# PowerSupply.net
KiCad netlist of a schematic drawn in Altium Designer
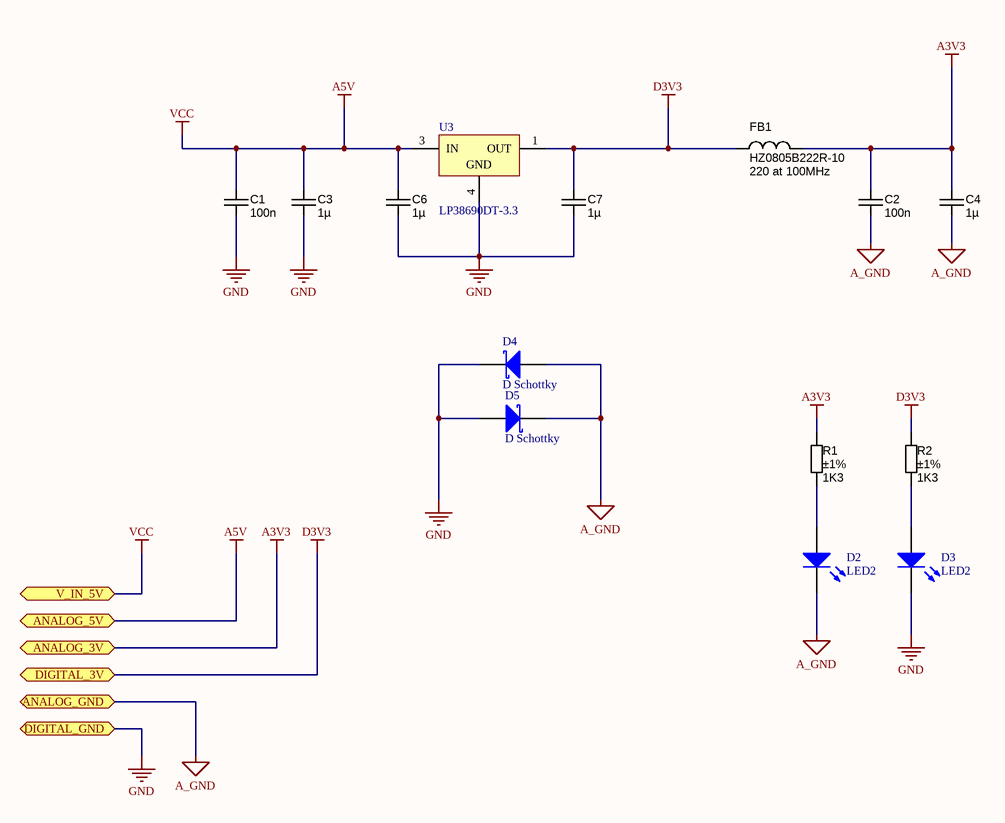
[diagram p0: PowerSupply.SchDoc]

(export (version "E")
  (design (tool "Eeschema 10.0.6"))
  (components
    (comp (ref "C1")
      (value "100n")
      (footprint "CAPC2012X135N")
      (description "Capacitor SMD Cer 100nF 10% 50V X7R 0805")
      (fields (field (name "TOLERANCE") "±10%") (field (name "Comment") "approved sub OK"))
      (libsource (lib "PBL - Capacitors") (part "CAPC_100n_0805_X7R_50V_10%"))
    )
    (comp (ref "C2")
      (value "100n")
      (footprint "CAPC2012X135N")
      (description "Capacitor SMD Cer 100nF 10% 50V X7R 0805")
      (fields (field (name "TOLERANCE") "±10%") (field (name "Comment") "approved sub OK"))
      (libsource (lib "PBL - Capacitors") (part "CAPC_100n_0805_X7R_50V_10%"))
    )
    (comp (ref "C3")
      (value "1µ")
      (footprint "CAPC2012X135N")
      (description "Capacitor SMD Cer 1uF 10% 16V X7R 0805")
      (fields (field (name "TOLERANCE") "±10%") (field (name "Comment") "approved sub OK"))
      (libsource (lib "PBL - Capacitors") (part "CAPC_1u_0805_X7R_16V_10%"))
    )
    (comp (ref "C4")
      (value "1µ")
      (footprint "CAPC2012X135N")
      (description "Capacitor SMD Cer 1uF 10% 16V X7R 0805")
      (fields (field (name "TOLERANCE") "±10%") (field (name "Comment") "approved sub OK"))
      (libsource (lib "PBL - Capacitors") (part "CAPC_1u_0805_X7R_16V_10%"))
    )
    (comp (ref "C6")
      (value "1µ")
      (footprint "CAPC2012X135N")
      (description "Capacitor SMD Cer 1uF 10% 16V X7R 0805")
      (fields (field (name "TOLERANCE") "±10%") (field (name "Comment") "approved sub OK"))
      (libsource (lib "PBL - Capacitors") (part "CAPC_1u_0805_X7R_16V_10%"))
    )
    (comp (ref "C7")
      (value "1µ")
      (footprint "CAPC2012X135N")
      (description "Capacitor SMD Cer 1uF 10% 16V X7R 0805")
      (fields (field (name "TOLERANCE") "±10%") (field (name "Comment") "approved sub OK"))
      (libsource (lib "PBL - Capacitors") (part "CAPC_1u_0805_X7R_16V_10%"))
    )
    (comp (ref "D2")
      (value "LED2")
      (footprint "3.2X1.6X1.1")
      (description "Typical RED, GREEN, YELLOW, AMBER GaAs LED")
      (fields (field (name "PUBLISHER") "Altium Limited"))
      (libsource (lib "Miscellaneous Devices") (part "LED2"))
    )
    (comp (ref "D3")
      (value "LED2")
      (footprint "3.2X1.6X1.1")
      (description "Typical RED, GREEN, YELLOW, AMBER GaAs LED")
      (fields (field (name "PUBLISHER") "Altium Limited"))
      (libsource (lib "Miscellaneous Devices") (part "LED2"))
    )
    (comp (ref "D4")
      (value "D Schottky")
      (footprint "LED-0805-A")
      (description "Schottky Diode")
      (fields (field (name "PUBLISHER") "Altium Limited"))
      (libsource (lib "Miscellaneous Devices") (part "D Schottky"))
    )
    (comp (ref "D5")
      (value "D Schottky")
      (footprint "LED-0805-A")
      (description "Schottky Diode")
      (fields (field (name "PUBLISHER") "Altium Limited"))
      (libsource (lib "Miscellaneous Devices") (part "D Schottky"))
    )
    (comp (ref "FB1")
      (value "220 at 100MHz")
      (footprint "FBC2012N")
      (description "Ferrite bead BLM21PG221SN1D 220 ohm at 100MHz 2A")
      (fields (field (name "MANUFACTURER PART NUMBER 1") "HZ0805B222R-10"))
      (libsource (lib "PBL - Inductors") (part "FERRITE_2K2-100MHz_0805"))
    )
    (comp (ref "R1")
      (value "1K3")
      (footprint "RESC2012X70N")
      (description "Resistor SMD chip 1.3k Ohm 0.125W 1% 0805")
      (fields (field (name "TOLERANCE") "±1%") (field (name "Comment") "Thick Film"))
      (libsource (lib "PBL - Resistors") (part "RES_1K3_0805_1%"))
    )
    (comp (ref "R2")
      (value "1K3")
      (footprint "RESC2012X70N")
      (description "Resistor SMD chip 1.3k Ohm 0.125W 1% 0805")
      (fields (field (name "TOLERANCE") "±1%") (field (name "Comment") "Thick Film"))
      (libsource (lib "PBL - Resistors") (part "RES_1K3_0805_1%"))
    )
    (comp (ref "U3")
      (value "LP38690DT-3.3")
      (footprint "TD03B_N")
      (description "1A Low Dropout CMOS Linear Regulators, 3-pin TO-252")
      (fields (field (name "MANUFACTURER") "National Semiconductor"))
      (libsource (lib "National Semiconductor LDO") (part "LP38690DT-3.3"))
    )
  )
  (nets
    (net (code "1") (name "A3V3") (class "Default")
      (node (ref "C2") (pin "1") (pintype "passive"))
      (node (ref "C4") (pin "1") (pintype "passive"))
      (node (ref "FB1") (pin "2") (pinfunction "2_2") (pintype "passive"))
      (node (ref "R1") (pin "1") (pinfunction "1_1") (pintype "passive"))
    )
    (net (code "2") (name "A5V") (class "Default")
      (node (ref "C1") (pin "1") (pintype "passive"))
      (node (ref "C3") (pin "1") (pintype "passive"))
      (node (ref "C6") (pin "1") (pintype "passive"))
      (node (ref "U3") (pin "3") (pinfunction "IN_3") (pintype "power_in"))
    )
    (net (code "3") (name "A_GND") (class "Default")
      (node (ref "C2") (pin "2") (pintype "passive"))
      (node (ref "C4") (pin "2") (pintype "passive"))
      (node (ref "D2") (pin "2") (pinfunction "K_2") (pintype "passive"))
      (node (ref "D4") (pin "1") (pinfunction "A_1") (pintype "passive"))
      (node (ref "D5") (pin "2") (pinfunction "K_2") (pintype "passive"))
    )
    (net (code "4") (name "D3V3") (class "Default")
      (node (ref "C7") (pin "1") (pintype "passive"))
      (node (ref "FB1") (pin "1") (pinfunction "1_1") (pintype "passive"))
      (node (ref "R2") (pin "1") (pinfunction "1_1") (pintype "passive"))
      (node (ref "U3") (pin "1") (pinfunction "OUT_1") (pintype "power_in"))
    )
    (net (code "5") (name "GND") (class "Default")
      (node (ref "C1") (pin "2") (pintype "passive"))
      (node (ref "C3") (pin "2") (pintype "passive"))
      (node (ref "C6") (pin "2") (pintype "passive"))
      (node (ref "C7") (pin "2") (pintype "passive"))
      (node (ref "D3") (pin "2") (pinfunction "K_2") (pintype "passive"))
      (node (ref "D4") (pin "2") (pinfunction "K_2") (pintype "passive"))
      (node (ref "D5") (pin "1") (pinfunction "A_1") (pintype "passive"))
      (node (ref "U3") (pin "4") (pinfunction "GND_4") (pintype "power_in"))
    )
    (net (code "6") (name "Net-(D2-A)") (class "Default")
      (node (ref "D2") (pin "1") (pinfunction "A_1") (pintype "passive"))
      (node (ref "R1") (pin "2") (pinfunction "2_2") (pintype "passive"))
    )
    (net (code "7") (name "Net-(D3-A)") (class "Default")
      (node (ref "D3") (pin "1") (pinfunction "A_1") (pintype "passive"))
      (node (ref "R2") (pin "2") (pinfunction "2_2") (pintype "passive"))
    )
  )
)
